# circuitdraft.net
KiCad netlist of a schematic drawn in EAGLE
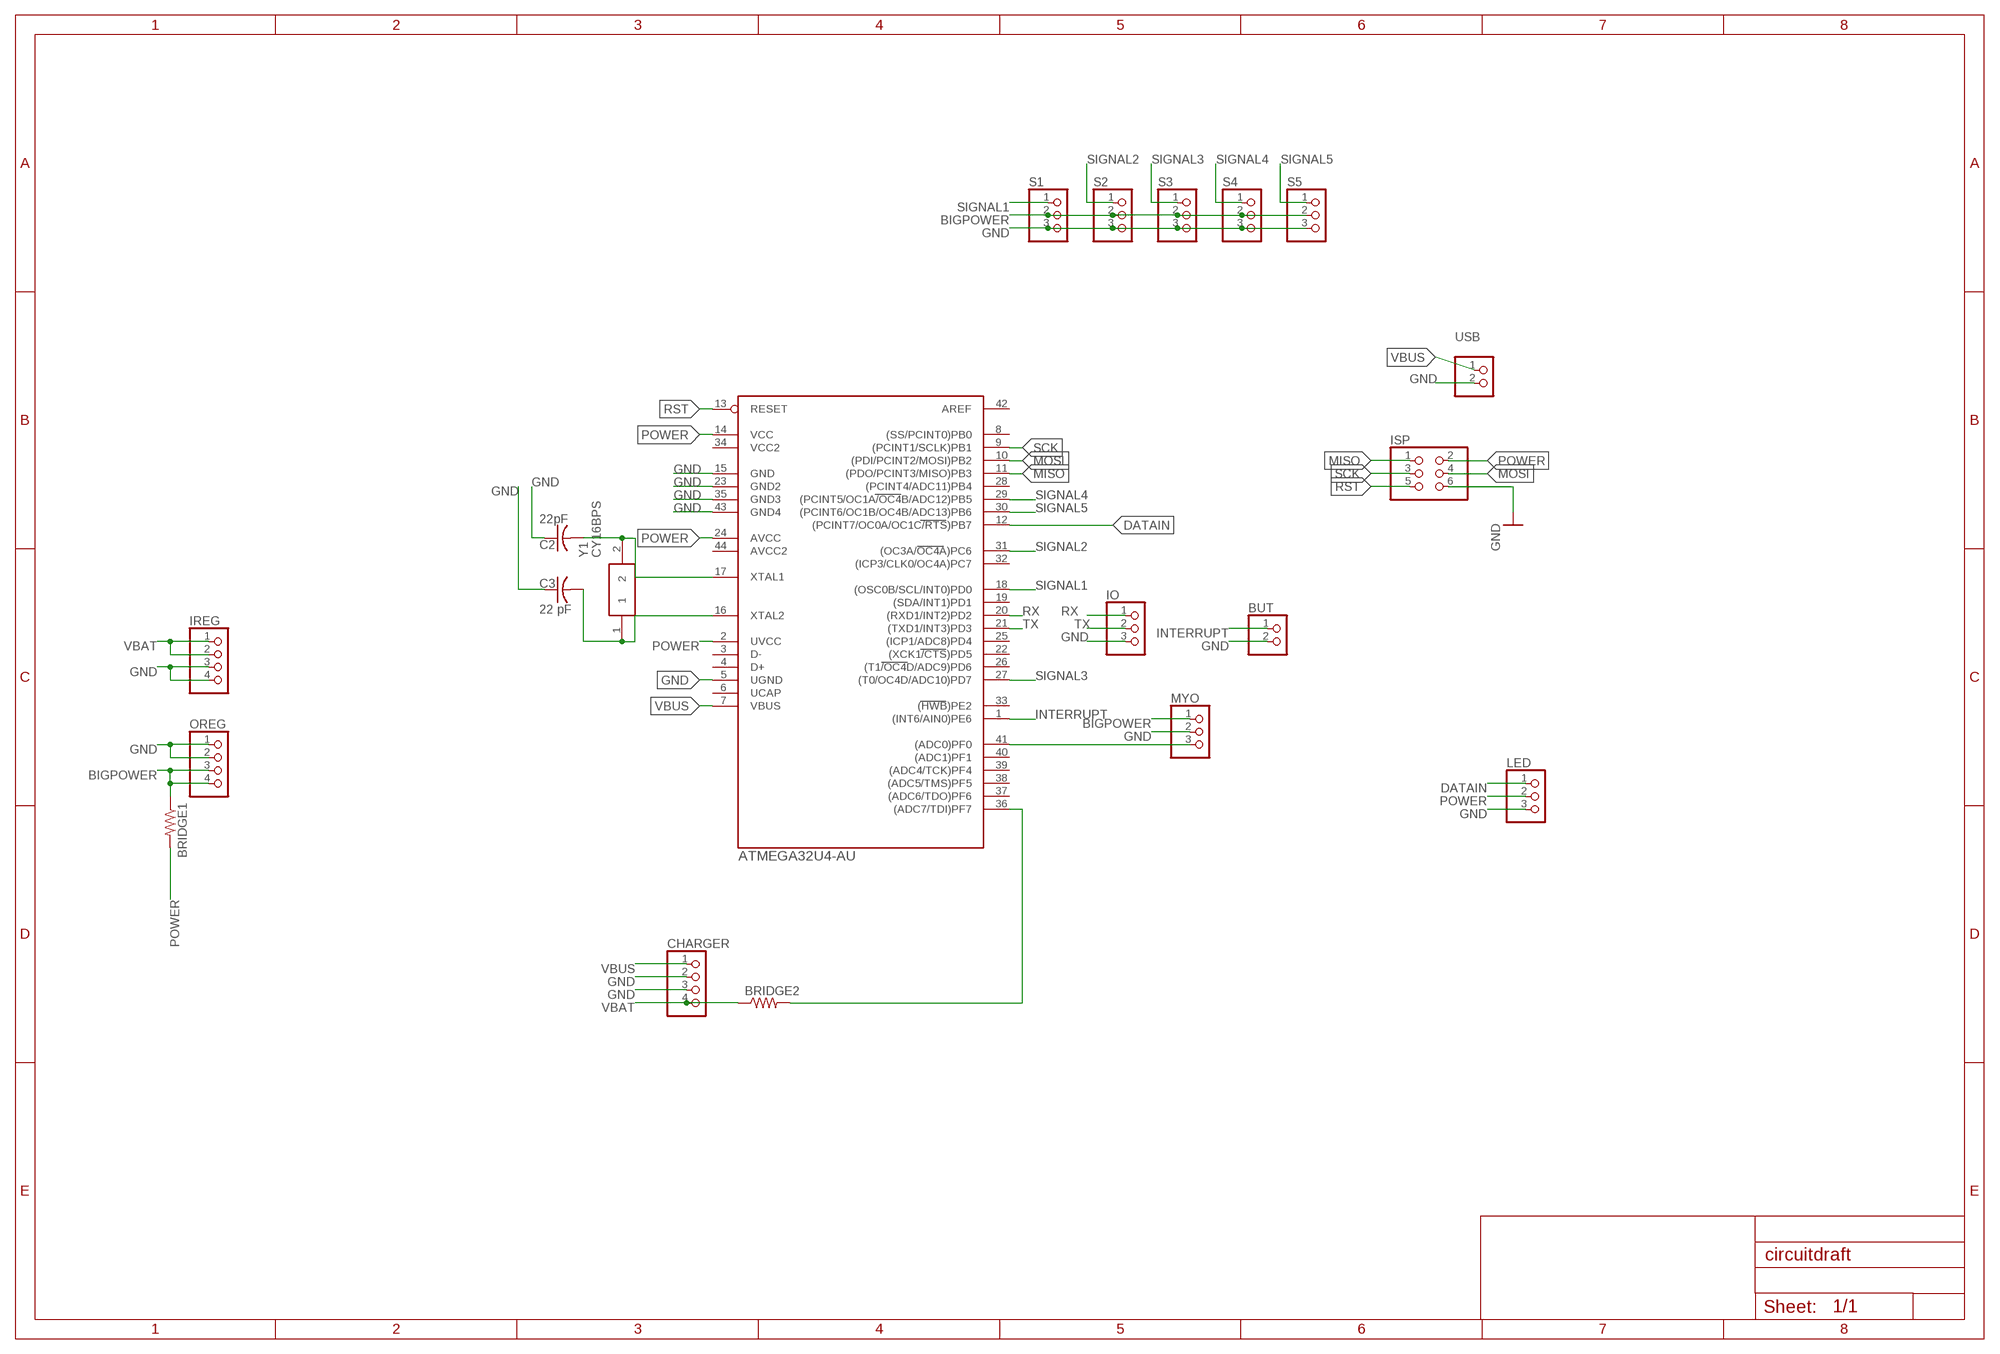
[diagram p0: schematic, sheet 1]

(export (version "E")
  (design (tool "Eeschema 10.0.6"))
  (components
    (comp (ref "BRIDGE1")
      (value "R-US_M0805")
      (footprint "eagle-import:M0805")
      (libsource (lib "eagle-import") (part "R-US_M0805"))
    )
    (comp (ref "BRIDGE2")
      (value "R-US_M0805")
      (footprint "eagle-import:M0805")
      (libsource (lib "eagle-import") (part "R-US_M0805"))
    )
    (comp (ref "BUT")
      (value "PINHD-1X2")
      (footprint "eagle-import:1X02")
      (libsource (lib "eagle-import") (part "PINHD-1X2"))
    )
    (comp (ref "C2")
      (value "22pF")
      (footprint "eagle-import:C025-024X044")
      (libsource (lib "eagle-import") (part "C-US025-024X044"))
    )
    (comp (ref "C3")
      (value "22 pF")
      (footprint "eagle-import:C025-024X044")
      (libsource (lib "eagle-import") (part "C-US025-024X044"))
    )
    (comp (ref "CHARGER")
      (value "PINHD-1X4")
      (footprint "eagle-import:1X04")
      (libsource (lib "eagle-import") (part "PINHD-1X4"))
    )
    (comp (ref "IO")
      (value "PINHD-1X3")
      (footprint "eagle-import:1X03")
      (libsource (lib "eagle-import") (part "PINHD-1X3"))
    )
    (comp (ref "IREG")
      (value "PINHD-1X4")
      (footprint "eagle-import:1X04")
      (libsource (lib "eagle-import") (part "PINHD-1X4"))
    )
    (comp (ref "ISP")
      (value "PINHD-2X3")
      (footprint "eagle-import:2X03")
      (libsource (lib "eagle-import") (part "PINHD-2X3"))
    )
    (comp (ref "LED")
      (value "PINHD-1X3")
      (footprint "eagle-import:1X03")
      (libsource (lib "eagle-import") (part "PINHD-1X3"))
    )
    (comp (ref "MYO")
      (value "PINHD-1X3")
      (footprint "eagle-import:1X03")
      (libsource (lib "eagle-import") (part "PINHD-1X3"))
    )
    (comp (ref "OREG")
      (value "PINHD-1X4")
      (footprint "eagle-import:1X04")
      (libsource (lib "eagle-import") (part "PINHD-1X4"))
    )
    (comp (ref "S1")
      (value "PINHD-1X3")
      (footprint "eagle-import:1X03")
      (libsource (lib "eagle-import") (part "PINHD-1X3"))
    )
    (comp (ref "S2")
      (value "PINHD-1X3")
      (footprint "eagle-import:1X03")
      (libsource (lib "eagle-import") (part "PINHD-1X3"))
    )
    (comp (ref "S3")
      (value "PINHD-1X3")
      (footprint "eagle-import:1X03")
      (libsource (lib "eagle-import") (part "PINHD-1X3"))
    )
    (comp (ref "S4")
      (value "PINHD-1X3")
      (footprint "eagle-import:1X03")
      (libsource (lib "eagle-import") (part "PINHD-1X3"))
    )
    (comp (ref "S5")
      (value "PINHD-1X3")
      (footprint "eagle-import:1X03")
      (libsource (lib "eagle-import") (part "PINHD-1X3"))
    )
    (comp (ref "U$1")
      (value "ATMEGA32U4-AU")
      (footprint "eagle-import:TQFP44")
      (libsource (lib "eagle-import") (part "ATMEGA32U4-AU"))
    )
    (comp (ref "USB")
      (value "PINHD-1X2")
      (footprint "eagle-import:1X02")
      (libsource (lib "eagle-import") (part "PINHD-1X2"))
    )
    (comp (ref "Y1")
      (value "CY16BPS")
      (footprint "eagle-import:CY16BPS")
      (fields (field (name "MOUSER_PART_NUMBER") "549-CY16BPS"))
      (libsource (lib "eagle-import") (part "CY16BPS"))
    )
  )
  (nets
    (net (code "1") (name "/BIGPOWER") (class "Default")
      (node (ref "BRIDGE1") (pin "1") (pinfunction "1_1") (pintype "passive"))
      (node (ref "MYO") (pin "1") (pinfunction "1_1") (pintype "passive"))
      (node (ref "OREG") (pin "3") (pinfunction "3_3") (pintype "passive"))
      (node (ref "OREG") (pin "4") (pinfunction "4_4") (pintype "passive"))
      (node (ref "S1") (pin "2") (pinfunction "2_2") (pintype "passive"))
      (node (ref "S2") (pin "2") (pinfunction "2_2") (pintype "passive"))
      (node (ref "S3") (pin "2") (pinfunction "2_2") (pintype "passive"))
      (node (ref "S4") (pin "2") (pinfunction "2_2") (pintype "passive"))
      (node (ref "S5") (pin "2") (pinfunction "2_2") (pintype "passive"))
    )
    (net (code "2") (name "/INTERRUPT") (class "Default")
      (node (ref "BUT") (pin "1") (pinfunction "1_1") (pintype "passive"))
      (node (ref "U$1") (pin "1") (pinfunction "(INT6/AIN0)PE6_1") (pintype "bidirectional"))
    )
    (net (code "3") (name "/RX") (class "Default")
      (node (ref "IO") (pin "1") (pinfunction "1_1") (pintype "passive"))
      (node (ref "U$1") (pin "20") (pinfunction "(RXD1/INT2)PD2_20") (pintype "bidirectional"))
    )
    (net (code "4") (name "/SIGNAL1") (class "Default")
      (node (ref "S1") (pin "1") (pinfunction "1_1") (pintype "passive"))
      (node (ref "U$1") (pin "18") (pinfunction "(OSC0B/SCL/INT0)PD0_18") (pintype "bidirectional"))
    )
    (net (code "5") (name "/SIGNAL2") (class "Default")
      (node (ref "S2") (pin "1") (pinfunction "1_1") (pintype "passive"))
      (node (ref "U$1") (pin "31") (pinfunction "(OC3A/OC4A)PC6_31") (pintype "bidirectional"))
    )
    (net (code "6") (name "/SIGNAL3") (class "Default")
      (node (ref "S3") (pin "1") (pinfunction "1_1") (pintype "passive"))
      (node (ref "U$1") (pin "27") (pinfunction "(T0/OC4D/ADC10)PD7_27") (pintype "bidirectional"))
    )
    (net (code "7") (name "/SIGNAL4") (class "Default")
      (node (ref "S4") (pin "1") (pinfunction "1_1") (pintype "passive"))
      (node (ref "U$1") (pin "29") (pinfunction "(PCINT5/OC1A/OC4B/ADC12)PB5_29") (pintype "bidirectional"))
    )
    (net (code "8") (name "/SIGNAL5") (class "Default")
      (node (ref "S5") (pin "1") (pinfunction "1_1") (pintype "passive"))
      (node (ref "U$1") (pin "30") (pinfunction "(PCINT6/OC1B/OC4B/ADC13)PB6_30") (pintype "bidirectional"))
    )
    (net (code "9") (name "/TX") (class "Default")
      (node (ref "IO") (pin "2") (pinfunction "2_2") (pintype "passive"))
      (node (ref "U$1") (pin "21") (pinfunction "(TXD1/INT3)PD3_21") (pintype "bidirectional"))
    )
    (net (code "10") (name "/VBAT") (class "Default")
      (node (ref "BRIDGE2") (pin "1") (pinfunction "1_1") (pintype "passive"))
      (node (ref "CHARGER") (pin "4") (pinfunction "4_4") (pintype "passive"))
      (node (ref "IREG") (pin "1") (pinfunction "1_1") (pintype "passive"))
      (node (ref "IREG") (pin "2") (pinfunction "2_2") (pintype "passive"))
    )
    (net (code "11") (name "DATAIN") (class "Default")
      (node (ref "LED") (pin "1") (pinfunction "1_1") (pintype "passive"))
      (node (ref "U$1") (pin "12") (pinfunction "(PCINT7/OC0A/OC1C/RTS)PB7_12") (pintype "bidirectional"))
    )
    (net (code "12") (name "GND") (class "Default")
      (node (ref "BUT") (pin "2") (pinfunction "2_2") (pintype "passive"))
      (node (ref "C2") (pin "1") (pinfunction "1_1") (pintype "passive"))
      (node (ref "C3") (pin "1") (pinfunction "1_1") (pintype "passive"))
      (node (ref "CHARGER") (pin "2") (pinfunction "2_2") (pintype "passive"))
      (node (ref "CHARGER") (pin "3") (pinfunction "3_3") (pintype "passive"))
      (node (ref "IO") (pin "3") (pinfunction "3_3") (pintype "passive"))
      (node (ref "IREG") (pin "3") (pinfunction "3_3") (pintype "passive"))
      (node (ref "IREG") (pin "4") (pinfunction "4_4") (pintype "passive"))
      (node (ref "ISP") (pin "6") (pinfunction "6_6") (pintype "passive"))
      (node (ref "LED") (pin "3") (pinfunction "3_3") (pintype "passive"))
      (node (ref "MYO") (pin "2") (pinfunction "2_2") (pintype "passive"))
      (node (ref "OREG") (pin "1") (pinfunction "1_1") (pintype "passive"))
      (node (ref "OREG") (pin "2") (pinfunction "2_2") (pintype "passive"))
      (node (ref "S1") (pin "3") (pinfunction "3_3") (pintype "passive"))
      (node (ref "S2") (pin "3") (pinfunction "3_3") (pintype "passive"))
      (node (ref "S3") (pin "3") (pinfunction "3_3") (pintype "passive"))
      (node (ref "S4") (pin "3") (pinfunction "3_3") (pintype "passive"))
      (node (ref "S5") (pin "3") (pinfunction "3_3") (pintype "passive"))
      (node (ref "U$1") (pin "15") (pinfunction "GND_15") (pintype "bidirectional"))
      (node (ref "U$1") (pin "23") (pinfunction "GND2_23") (pintype "bidirectional"))
      (node (ref "U$1") (pin "35") (pinfunction "GND3_35") (pintype "bidirectional"))
      (node (ref "U$1") (pin "43") (pinfunction "GND4_43") (pintype "bidirectional"))
      (node (ref "U$1") (pin "5") (pinfunction "UGND_5") (pintype "bidirectional"))
      (node (ref "USB") (pin "2") (pinfunction "2_2") (pintype "passive"))
    )
    (net (code "13") (name "MISO") (class "Default")
      (node (ref "ISP") (pin "1") (pinfunction "1_1") (pintype "passive"))
      (node (ref "U$1") (pin "11") (pinfunction "(PDO/PCINT3/MISO)PB3_11") (pintype "bidirectional"))
    )
    (net (code "14") (name "MOSI") (class "Default")
      (node (ref "ISP") (pin "4") (pinfunction "4_4") (pintype "passive"))
      (node (ref "U$1") (pin "10") (pinfunction "(PDI/PCINT2/MOSI)PB2_10") (pintype "bidirectional"))
    )
    (net (code "15") (name "Net-(U$1-(ADC0)PF0)") (class "Default")
      (node (ref "MYO") (pin "3") (pinfunction "3_3") (pintype "passive"))
      (node (ref "U$1") (pin "41") (pinfunction "(ADC0)PF0_41") (pintype "bidirectional"))
    )
    (net (code "16") (name "Net-(U$1-(ADC7{slash}TDI)PF7)") (class "Default")
      (node (ref "BRIDGE2") (pin "2") (pinfunction "2_2") (pintype "passive"))
      (node (ref "U$1") (pin "36") (pinfunction "(ADC7/TDI)PF7_36") (pintype "bidirectional"))
    )
    (net (code "17") (name "Net-(U$1-XTAL1)") (class "Default")
      (node (ref "C2") (pin "2") (pinfunction "2_2") (pintype "passive"))
      (node (ref "U$1") (pin "17") (pinfunction "XTAL1_17") (pintype "bidirectional"))
      (node (ref "Y1") (pin "2") (pinfunction "2_2") (pintype "bidirectional"))
    )
    (net (code "18") (name "Net-(U$1-XTAL2)") (class "Default")
      (node (ref "C3") (pin "2") (pinfunction "2_2") (pintype "passive"))
      (node (ref "U$1") (pin "16") (pinfunction "XTAL2_16") (pintype "bidirectional"))
      (node (ref "Y1") (pin "1") (pinfunction "1_1") (pintype "bidirectional"))
    )
    (net (code "19") (name "POWER") (class "Default")
      (node (ref "BRIDGE1") (pin "2") (pinfunction "2_2") (pintype "passive"))
      (node (ref "ISP") (pin "2") (pinfunction "2_2") (pintype "passive"))
      (node (ref "LED") (pin "2") (pinfunction "2_2") (pintype "passive"))
      (node (ref "U$1") (pin "14") (pinfunction "VCC_14") (pintype "bidirectional"))
      (node (ref "U$1") (pin "2") (pinfunction "UVCC_2") (pintype "bidirectional"))
      (node (ref "U$1") (pin "24") (pinfunction "AVCC_24") (pintype "bidirectional"))
    )
    (net (code "20") (name "RST") (class "Default")
      (node (ref "ISP") (pin "5") (pinfunction "5_5") (pintype "passive"))
      (node (ref "U$1") (pin "13") (pinfunction "RESET_13") (pintype "bidirectional"))
    )
    (net (code "21") (name "SCK") (class "Default")
      (node (ref "ISP") (pin "3") (pinfunction "3_3") (pintype "passive"))
      (node (ref "U$1") (pin "9") (pinfunction "(PCINT1/SCLK)PB1_9") (pintype "bidirectional"))
    )
    (net (code "22") (name "VBUS") (class "Default")
      (node (ref "CHARGER") (pin "1") (pinfunction "1_1") (pintype "passive"))
      (node (ref "U$1") (pin "7") (pinfunction "VBUS_7") (pintype "bidirectional"))
      (node (ref "USB") (pin "1") (pinfunction "1_1") (pintype "passive"))
    )
    (net (code "23") (name "unconnected-(U$1-(ADC1)PF1-Pad40)") (class "Default")
      (node (ref "U$1") (pin "40") (pinfunction "(ADC1)PF1_40") (pintype "bidirectional"))
    )
    (net (code "24") (name "unconnected-(U$1-(ADC4{slash}TCK)PF4-Pad39)") (class "Default")
      (node (ref "U$1") (pin "39") (pinfunction "(ADC4/TCK)PF4_39") (pintype "bidirectional"))
    )
    (net (code "25") (name "unconnected-(U$1-(ADC5{slash}TMS)PF5-Pad38)") (class "Default")
      (node (ref "U$1") (pin "38") (pinfunction "(ADC5/TMS)PF5_38") (pintype "bidirectional"))
    )
    (net (code "26") (name "unconnected-(U$1-(ADC6{slash}TDO)PF6-Pad37)") (class "Default")
      (node (ref "U$1") (pin "37") (pinfunction "(ADC6/TDO)PF6_37") (pintype "bidirectional"))
    )
    (net (code "27") (name "unconnected-(U$1-(HWB)PE2-Pad33)") (class "Default")
      (node (ref "U$1") (pin "33") (pinfunction "(HWB)PE2_33") (pintype "bidirectional"))
    )
    (net (code "28") (name "unconnected-(U$1-(ICP1{slash}ADC8)PD4-Pad25)") (class "Default")
      (node (ref "U$1") (pin "25") (pinfunction "(ICP1/ADC8)PD4_25") (pintype "bidirectional"))
    )
    (net (code "29") (name "unconnected-(U$1-(ICP3{slash}CLK0{slash}OC4A)PC7-Pad32)") (class "Default")
      (node (ref "U$1") (pin "32") (pinfunction "(ICP3/CLK0/OC4A)PC7_32") (pintype "bidirectional"))
    )
    (net (code "30") (name "unconnected-(U$1-(PCINT4{slash}ADC11)PB4-Pad28)") (class "Default")
      (node (ref "U$1") (pin "28") (pinfunction "(PCINT4/ADC11)PB4_28") (pintype "bidirectional"))
    )
    (net (code "31") (name "unconnected-(U$1-(SDA{slash}INT1)PD1-Pad19)") (class "Default")
      (node (ref "U$1") (pin "19") (pinfunction "(SDA/INT1)PD1_19") (pintype "bidirectional"))
    )
    (net (code "32") (name "unconnected-(U$1-(SS{slash}PCINT0)PB0-Pad8)") (class "Default")
      (node (ref "U$1") (pin "8") (pinfunction "(SS/PCINT0)PB0_8") (pintype "bidirectional"))
    )
    (net (code "33") (name "unconnected-(U$1-(T1{slash}OC4D{slash}ADC9)PD6-Pad26)") (class "Default")
      (node (ref "U$1") (pin "26") (pinfunction "(T1/OC4D/ADC9)PD6_26") (pintype "bidirectional"))
    )
    (net (code "34") (name "unconnected-(U$1-(XCK1{slash}CTS)PD5-Pad22)") (class "Default")
      (node (ref "U$1") (pin "22") (pinfunction "(XCK1/CTS)PD5_22") (pintype "bidirectional"))
    )
    (net (code "35") (name "unconnected-(U$1-AREF-Pad42)") (class "Default")
      (node (ref "U$1") (pin "42") (pinfunction "AREF_42") (pintype "bidirectional"))
    )
    (net (code "36") (name "unconnected-(U$1-AVCC2-Pad44)") (class "Default")
      (node (ref "U$1") (pin "44") (pinfunction "AVCC2_44") (pintype "bidirectional"))
    )
    (net (code "37") (name "unconnected-(U$1-D+-Pad4)") (class "Default")
      (node (ref "U$1") (pin "4") (pinfunction "D+_4") (pintype "bidirectional"))
    )
    (net (code "38") (name "unconnected-(U$1-D--Pad3)") (class "Default")
      (node (ref "U$1") (pin "3") (pinfunction "D-_3") (pintype "bidirectional"))
    )
    (net (code "39") (name "unconnected-(U$1-UCAP-Pad6)") (class "Default")
      (node (ref "U$1") (pin "6") (pinfunction "UCAP_6") (pintype "bidirectional"))
    )
    (net (code "40") (name "unconnected-(U$1-VCC2-Pad34)") (class "Default")
      (node (ref "U$1") (pin "34") (pinfunction "VCC2_34") (pintype "bidirectional"))
    )
  )
)
